# wheelSense_revA.net
KiCad netlist of a schematic drawn in EAGLE
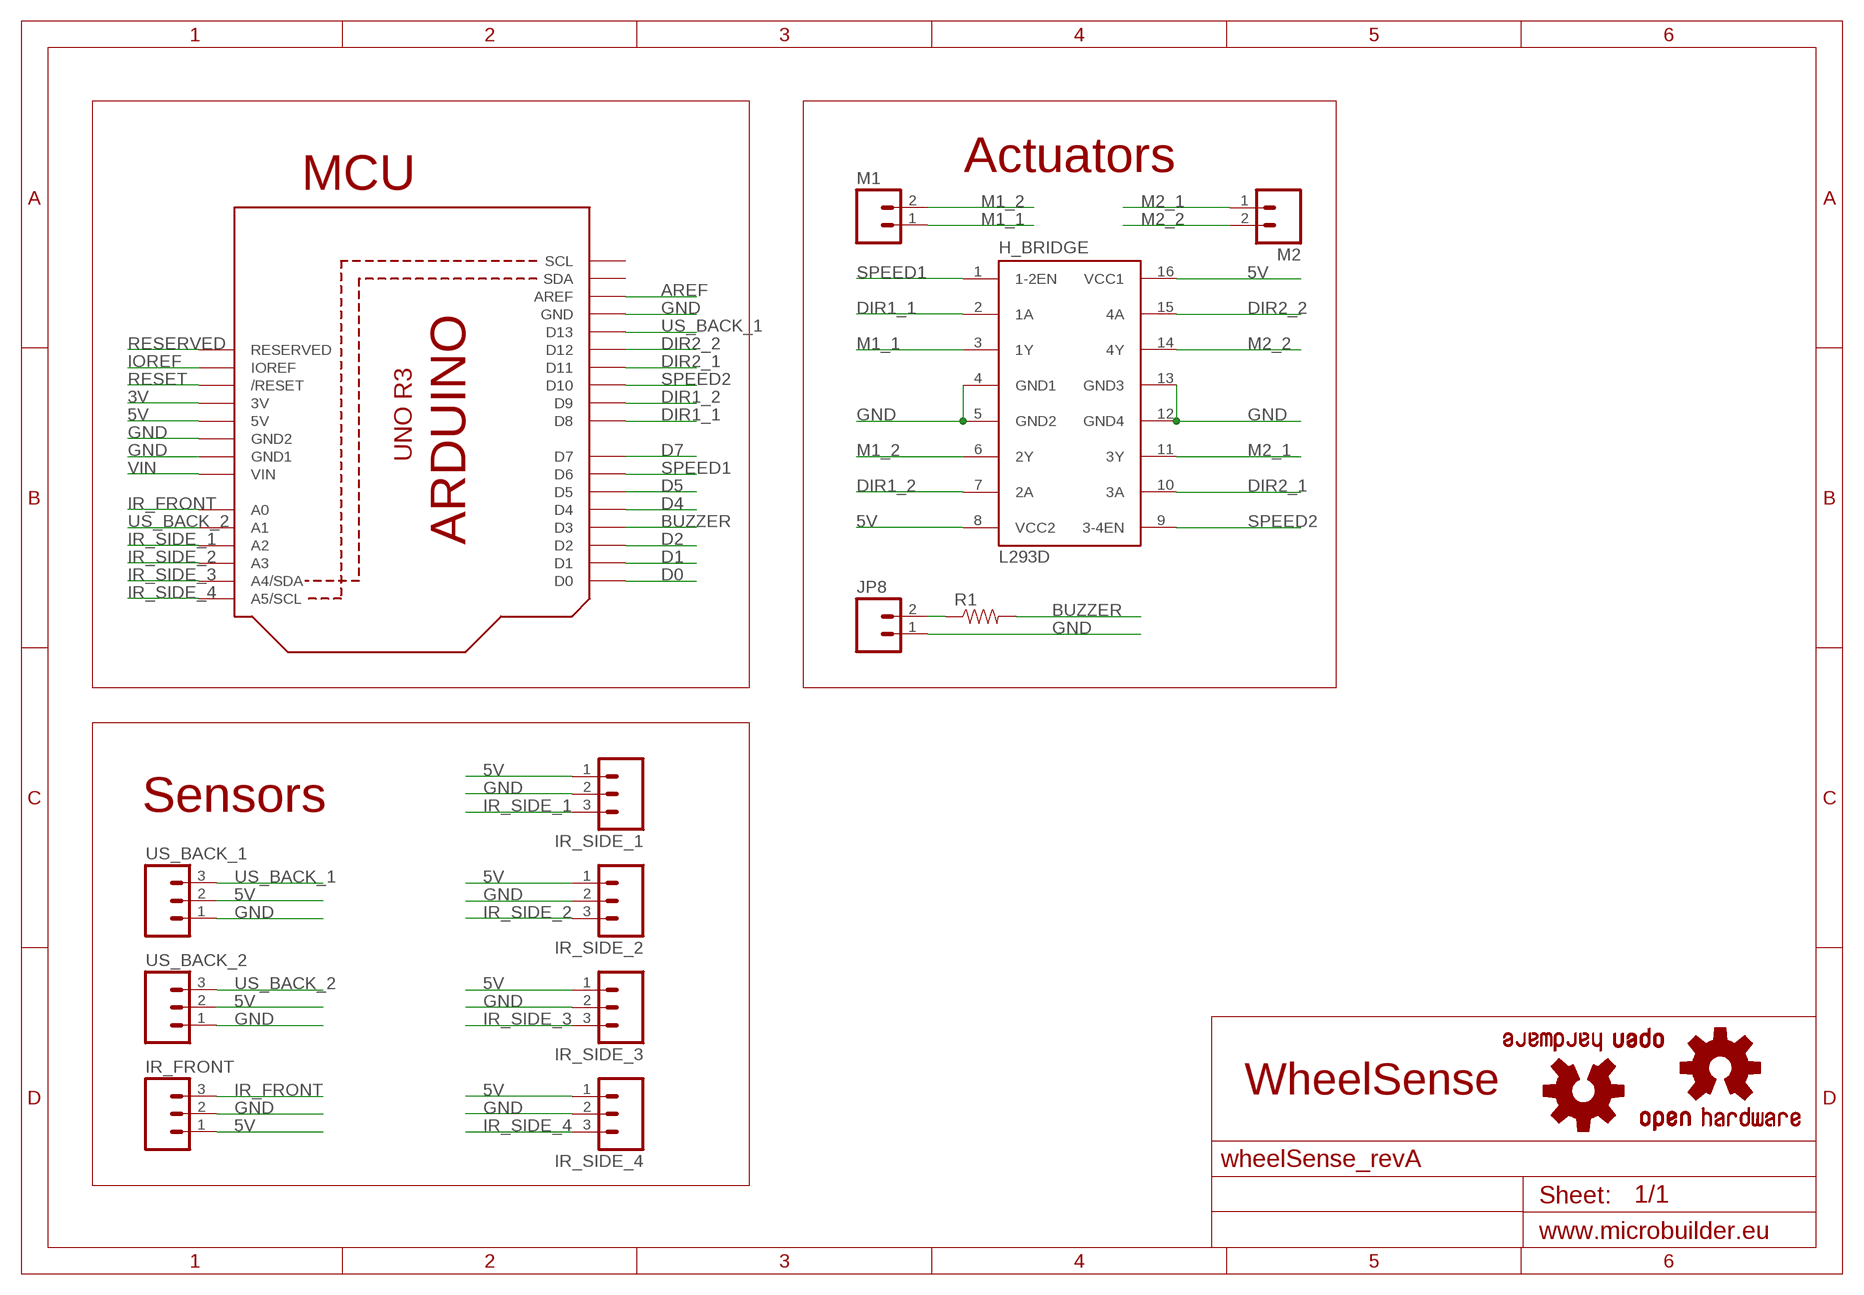
[diagram p0: schematic, sheet 1]

(export (version "E")
  (design (tool "Eeschema 10.0.6"))
  (components
    (comp (ref "H_BRIDGE")
      (value "L293D")
      (footprint "eagle-import:DIL16")
      (libsource (lib "eagle-import") (part "L293D"))
    )
    (comp (ref "IR_FRONT")
      (value "M03POLAR")
      (footprint "eagle-import:MOLEX-1X3")
      (libsource (lib "eagle-import") (part "M03POLAR"))
    )
    (comp (ref "IR_SIDE_1")
      (value "M03POLAR")
      (footprint "eagle-import:MOLEX-1X3")
      (libsource (lib "eagle-import") (part "M03POLAR"))
    )
    (comp (ref "IR_SIDE_2")
      (value "M03POLAR")
      (footprint "eagle-import:MOLEX-1X3")
      (libsource (lib "eagle-import") (part "M03POLAR"))
    )
    (comp (ref "IR_SIDE_3")
      (value "M03POLAR")
      (footprint "eagle-import:MOLEX-1X3")
      (libsource (lib "eagle-import") (part "M03POLAR"))
    )
    (comp (ref "IR_SIDE_4")
      (value "M03POLAR")
      (footprint "eagle-import:MOLEX-1X3")
      (libsource (lib "eagle-import") (part "M03POLAR"))
    )
    (comp (ref "JP8")
      (value "M02POLAR")
      (footprint "eagle-import:MOLEX-1X2")
      (libsource (lib "eagle-import") (part "M02POLAR"))
    )
    (comp (ref "LOGO1")
      (value "OSHW-LOGOL-TOP")
      (footprint "eagle-import:OSHW_LOGO_L_TOP")
      (libsource (lib "eagle-import") (part "OSHW-LOGOL-TOP"))
    )
    (comp (ref "LOGO2")
      (value "OSHW-LOGOL-TOP")
      (footprint "eagle-import:OSHW_LOGO_L_TOP")
      (libsource (lib "eagle-import") (part "OSHW-LOGOL-TOP"))
    )
    (comp (ref "M1")
      (value "M02POLAR")
      (footprint "eagle-import:MOLEX-1X2")
      (libsource (lib "eagle-import") (part "M02POLAR"))
    )
    (comp (ref "M2")
      (value "M02POLAR")
      (footprint "eagle-import:MOLEX-1X2")
      (libsource (lib "eagle-import") (part "M02POLAR"))
    )
    (comp (ref "R1")
      (value "RESISTORPTH-1/4W")
      (footprint "eagle-import:AXIAL-0.4")
      (libsource (lib "eagle-import") (part "RESISTORPTH-1/4W"))
    )
    (comp (ref "U$1")
      (value "ARDUIN0R3_NOHOLES")
      (footprint "eagle-import:ARDUINOR3-NOHOLES")
      (libsource (lib "eagle-import") (part "ARDUIN0R3_NOHOLES"))
    )
    (comp (ref "US_BACK_1")
      (value "M03POLAR")
      (footprint "eagle-import:MOLEX-1X3")
      (libsource (lib "eagle-import") (part "M03POLAR"))
    )
    (comp (ref "US_BACK_2")
      (value "M03POLAR")
      (footprint "eagle-import:MOLEX-1X3")
      (libsource (lib "eagle-import") (part "M03POLAR"))
    )
  )
  (nets
    (net (code "1") (name "/3V") (class "Default")
      (node (ref "U$1") (pin "3V") (pinfunction "3V_3V") (pintype "power_in"))
    )
    (net (code "2") (name "/5V") (class "Default")
      (node (ref "H_BRIDGE") (pin "16") (pinfunction "VCC1_16") (pintype "power_in"))
      (node (ref "H_BRIDGE") (pin "8") (pinfunction "VCC2_8") (pintype "power_in"))
      (node (ref "IR_FRONT") (pin "1") (pinfunction "1_1") (pintype "passive"))
      (node (ref "IR_SIDE_1") (pin "1") (pinfunction "1_1") (pintype "passive"))
      (node (ref "IR_SIDE_2") (pin "1") (pinfunction "1_1") (pintype "passive"))
      (node (ref "IR_SIDE_3") (pin "1") (pinfunction "1_1") (pintype "passive"))
      (node (ref "IR_SIDE_4") (pin "1") (pinfunction "1_1") (pintype "passive"))
      (node (ref "U$1") (pin "5V") (pinfunction "5V_5V") (pintype "power_in"))
      (node (ref "US_BACK_1") (pin "2") (pinfunction "2_2") (pintype "passive"))
      (node (ref "US_BACK_2") (pin "2") (pinfunction "2_2") (pintype "passive"))
    )
    (net (code "3") (name "/AREF") (class "Default")
      (node (ref "U$1") (pin "AREF") (pinfunction "AREF_AREF") (pintype "bidirectional"))
    )
    (net (code "4") (name "/BUZZER") (class "Default")
      (node (ref "R1") (pin "P$2") (pinfunction "2_P$2") (pintype "passive"))
      (node (ref "U$1") (pin "D3") (pinfunction "D3_D3") (pintype "bidirectional"))
    )
    (net (code "5") (name "/D0") (class "Default")
      (node (ref "U$1") (pin "D0") (pinfunction "D0_D0") (pintype "bidirectional"))
    )
    (net (code "6") (name "/D1") (class "Default")
      (node (ref "U$1") (pin "D1") (pinfunction "D1_D1") (pintype "bidirectional"))
    )
    (net (code "7") (name "/D2") (class "Default")
      (node (ref "U$1") (pin "D2") (pinfunction "D2_D2") (pintype "bidirectional"))
    )
    (net (code "8") (name "/D4") (class "Default")
      (node (ref "U$1") (pin "D4") (pinfunction "D4_D4") (pintype "bidirectional"))
    )
    (net (code "9") (name "/D5") (class "Default")
      (node (ref "U$1") (pin "D5") (pinfunction "D5_D5") (pintype "bidirectional"))
    )
    (net (code "10") (name "/D7") (class "Default")
      (node (ref "U$1") (pin "D7") (pinfunction "D7_D7") (pintype "bidirectional"))
    )
    (net (code "11") (name "/DIR1_1") (class "Default")
      (node (ref "H_BRIDGE") (pin "2") (pinfunction "1A_2") (pintype "input"))
      (node (ref "U$1") (pin "D8") (pinfunction "D8_D8") (pintype "bidirectional"))
    )
    (net (code "12") (name "/DIR1_2") (class "Default")
      (node (ref "H_BRIDGE") (pin "7") (pinfunction "2A_7") (pintype "input"))
      (node (ref "U$1") (pin "D9") (pinfunction "D9_D9") (pintype "bidirectional"))
    )
    (net (code "13") (name "/DIR2_1") (class "Default")
      (node (ref "H_BRIDGE") (pin "10") (pinfunction "3A_10") (pintype "input"))
      (node (ref "U$1") (pin "D11") (pinfunction "D11_D11") (pintype "bidirectional"))
    )
    (net (code "14") (name "/DIR2_2") (class "Default")
      (node (ref "H_BRIDGE") (pin "15") (pinfunction "4A_15") (pintype "input"))
      (node (ref "U$1") (pin "D12") (pinfunction "D12_D12") (pintype "bidirectional"))
    )
    (net (code "15") (name "/GND") (class "Default")
      (node (ref "H_BRIDGE") (pin "12") (pinfunction "GND4_12") (pintype "power_in"))
      (node (ref "H_BRIDGE") (pin "13") (pinfunction "GND3_13") (pintype "power_in"))
      (node (ref "H_BRIDGE") (pin "4") (pinfunction "GND1_4") (pintype "power_in"))
      (node (ref "H_BRIDGE") (pin "5") (pinfunction "GND2_5") (pintype "power_in"))
      (node (ref "IR_FRONT") (pin "2") (pinfunction "2_2") (pintype "passive"))
      (node (ref "IR_SIDE_1") (pin "2") (pinfunction "2_2") (pintype "passive"))
      (node (ref "IR_SIDE_2") (pin "2") (pinfunction "2_2") (pintype "passive"))
      (node (ref "IR_SIDE_3") (pin "2") (pinfunction "2_2") (pintype "passive"))
      (node (ref "IR_SIDE_4") (pin "2") (pinfunction "2_2") (pintype "passive"))
      (node (ref "JP8") (pin "1") (pinfunction "1_1") (pintype "passive"))
      (node (ref "U$1") (pin "GND") (pinfunction "GND_GND") (pintype "power_in"))
      (node (ref "U$1") (pin "GND1") (pinfunction "GND1_GND1") (pintype "power_in"))
      (node (ref "U$1") (pin "GND2") (pinfunction "GND2_GND2") (pintype "power_in"))
      (node (ref "US_BACK_1") (pin "1") (pinfunction "1_1") (pintype "passive"))
      (node (ref "US_BACK_2") (pin "1") (pinfunction "1_1") (pintype "passive"))
    )
    (net (code "16") (name "/IOREF") (class "Default")
      (node (ref "U$1") (pin "IOREF") (pinfunction "IOREF_IOREF") (pintype "output"))
    )
    (net (code "17") (name "/IR_FRONT") (class "Default")
      (node (ref "IR_FRONT") (pin "3") (pinfunction "3_3") (pintype "passive"))
      (node (ref "U$1") (pin "A0") (pinfunction "A0_A0") (pintype "bidirectional"))
    )
    (net (code "18") (name "/IR_SIDE_1") (class "Default")
      (node (ref "IR_SIDE_1") (pin "3") (pinfunction "3_3") (pintype "passive"))
      (node (ref "U$1") (pin "A2") (pinfunction "A2_A2") (pintype "bidirectional"))
    )
    (net (code "19") (name "/IR_SIDE_2") (class "Default")
      (node (ref "IR_SIDE_2") (pin "3") (pinfunction "3_3") (pintype "passive"))
      (node (ref "U$1") (pin "A3") (pinfunction "A3_A3") (pintype "bidirectional"))
    )
    (net (code "20") (name "/IR_SIDE_3") (class "Default")
      (node (ref "IR_SIDE_3") (pin "3") (pinfunction "3_3") (pintype "passive"))
      (node (ref "U$1") (pin "A4") (pinfunction "A4/SDA_A4") (pintype "bidirectional"))
    )
    (net (code "21") (name "/IR_SIDE_4") (class "Default")
      (node (ref "IR_SIDE_4") (pin "3") (pinfunction "3_3") (pintype "passive"))
      (node (ref "U$1") (pin "A5") (pinfunction "A5/SCL_A5") (pintype "bidirectional"))
    )
    (net (code "22") (name "/M1_1") (class "Default")
      (node (ref "H_BRIDGE") (pin "3") (pinfunction "1Y_3") (pintype "output"))
      (node (ref "M1") (pin "1") (pinfunction "1_1") (pintype "passive"))
    )
    (net (code "23") (name "/M1_2") (class "Default")
      (node (ref "H_BRIDGE") (pin "6") (pinfunction "2Y_6") (pintype "output"))
      (node (ref "M1") (pin "2") (pinfunction "2_2") (pintype "passive"))
    )
    (net (code "24") (name "/M2_1") (class "Default")
      (node (ref "H_BRIDGE") (pin "11") (pinfunction "3Y_11") (pintype "output"))
      (node (ref "M2") (pin "1") (pinfunction "1_1") (pintype "passive"))
    )
    (net (code "25") (name "/M2_2") (class "Default")
      (node (ref "H_BRIDGE") (pin "14") (pinfunction "4Y_14") (pintype "output"))
      (node (ref "M2") (pin "2") (pinfunction "2_2") (pintype "passive"))
    )
    (net (code "27") (name "/RESERVED") (class "Default")
      (node (ref "U$1") (pin "RESERVED") (pinfunction "RESERVED_RESERVED") (pintype "no_connect"))
    )
    (net (code "28") (name "/RESET") (class "Default")
      (node (ref "U$1") (pin "RESET") (pinfunction "/RESET_RESET") (pintype "bidirectional"))
    )
    (net (code "29") (name "/SPEED1") (class "Default")
      (node (ref "H_BRIDGE") (pin "1") (pinfunction "1-2EN_1") (pintype "input"))
      (node (ref "U$1") (pin "D6") (pinfunction "D6_D6") (pintype "bidirectional"))
    )
    (net (code "30") (name "/SPEED2") (class "Default")
      (node (ref "H_BRIDGE") (pin "9") (pinfunction "3-4EN_9") (pintype "input"))
      (node (ref "U$1") (pin "D10") (pinfunction "D10_D10") (pintype "bidirectional"))
    )
    (net (code "31") (name "/US_BACK_1") (class "Default")
      (node (ref "U$1") (pin "D13") (pinfunction "D13_D13") (pintype "bidirectional"))
      (node (ref "US_BACK_1") (pin "3") (pinfunction "3_3") (pintype "passive"))
    )
    (net (code "32") (name "/US_BACK_2") (class "Default")
      (node (ref "U$1") (pin "A1") (pinfunction "A1_A1") (pintype "bidirectional"))
      (node (ref "US_BACK_2") (pin "3") (pinfunction "3_3") (pintype "passive"))
    )
    (net (code "33") (name "/VIN") (class "Default")
      (node (ref "U$1") (pin "VIN") (pinfunction "VIN_VIN") (pintype "power_in"))
    )
    (net (code "34") (name "Net-(R1-1)") (class "Default")
      (node (ref "JP8") (pin "2") (pinfunction "2_2") (pintype "passive"))
      (node (ref "R1") (pin "P$1") (pinfunction "1_P$1") (pintype "passive"))
    )
    (net (code "35") (name "unconnected-(U$1-PadSCL)") (class "Default")
      (node (ref "U$1") (pin "SCL") (pinfunction "SCL_SCL") (pintype "bidirectional"))
    )
    (net (code "36") (name "unconnected-(U$1-PadSDA)") (class "Default")
      (node (ref "U$1") (pin "SDA") (pinfunction "SDA_SDA") (pintype "bidirectional"))
    )
  )
)
